# CubieBoardVGABreakout.net
KiCad netlist of a schematic drawn in EAGLE
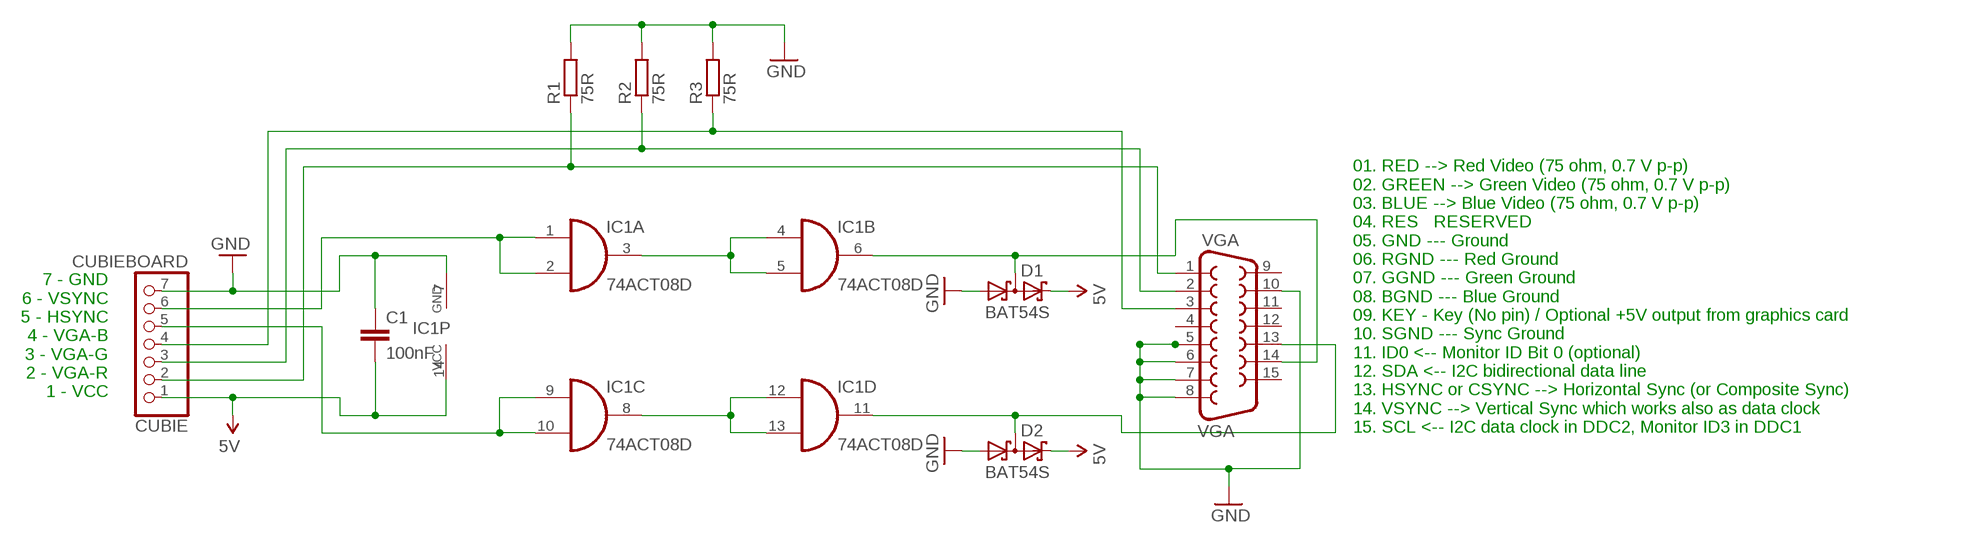
[diagram p0: schematic, sheet 1]

(export (version "E")
  (design (tool "Eeschema 10.0.6"))
  (components
    (comp (ref "C1")
      (value "100nF")
      (footprint "eagle-import:0805")
      (libsource (lib "eagle-import") (part "CAP0805"))
    )
    (comp (ref "CUBIE")
      (value "CUBIEBOARD")
      (footprint "eagle-import:1X07")
      (libsource (lib "eagle-import") (part "PINHD-1X7"))
    )
    (comp (ref "D1")
      (value "BAT54S")
      (footprint "eagle-import:SOT23")
      (libsource (lib "eagle-import") (part "BAT54S"))
    )
    (comp (ref "D2")
      (value "BAT54S")
      (footprint "eagle-import:SOT23")
      (libsource (lib "eagle-import") (part "BAT54S"))
    )
    (comp (ref "IC1")
      (value "74ACT08D")
      (footprint "eagle-import:SO14")
      (libsource (lib "eagle-import") (part "7408DACT"))
    )
    (comp (ref "R1")
      (value "75R")
      (footprint "eagle-import:0204V")
      (libsource (lib "eagle-import") (part "R-EU_0204/2V"))
    )
    (comp (ref "R2")
      (value "75R")
      (footprint "eagle-import:0204V")
      (libsource (lib "eagle-import") (part "R-EU_0204/2V"))
    )
    (comp (ref "R3")
      (value "75R")
      (footprint "eagle-import:0204V")
      (libsource (lib "eagle-import") (part "R-EU_0204/2V"))
    )
    (comp (ref "VGA")
      (value "VGA")
      (footprint "eagle-import:HDF15H")
      (libsource (lib "eagle-import") (part "F15HDH"))
    )
  )
  (nets
    (net (code "1") (name "5V") (class "Default")
      (node (ref "C1") (pin "2") (pinfunction "2_2") (pintype "passive"))
      (node (ref "CUBIE") (pin "1") (pinfunction "1_1") (pintype "passive"))
      (node (ref "D1") (pin "2") (pinfunction "C2_2") (pintype "passive"))
      (node (ref "D2") (pin "2") (pinfunction "C2_2") (pintype "passive"))
      (node (ref "IC1") (pin "14") (pinfunction "VCC_14") (pintype "power_in"))
    )
    (net (code "2") (name "GND") (class "Default")
      (node (ref "C1") (pin "1") (pinfunction "1_1") (pintype "passive"))
      (node (ref "CUBIE") (pin "7") (pinfunction "7_7") (pintype "passive"))
      (node (ref "D1") (pin "1") (pinfunction "A1_1") (pintype "passive"))
      (node (ref "D2") (pin "1") (pinfunction "A1_1") (pintype "passive"))
      (node (ref "IC1") (pin "7") (pinfunction "GND_7") (pintype "power_in"))
      (node (ref "R1") (pin "2") (pinfunction "2_2") (pintype "passive"))
      (node (ref "R2") (pin "2") (pinfunction "2_2") (pintype "passive"))
      (node (ref "R3") (pin "2") (pinfunction "2_2") (pintype "passive"))
      (node (ref "VGA") (pin "10") (pinfunction "10_10") (pintype "passive"))
      (node (ref "VGA") (pin "5") (pinfunction "5_5") (pintype "passive"))
      (node (ref "VGA") (pin "6") (pinfunction "6_6") (pintype "passive"))
      (node (ref "VGA") (pin "7") (pinfunction "7_7") (pintype "passive"))
      (node (ref "VGA") (pin "8") (pinfunction "8_8") (pintype "passive"))
    )
    (net (code "3") (name "Net-(CUBIE-Pad2)") (class "Default")
      (node (ref "CUBIE") (pin "2") (pinfunction "2_2") (pintype "passive"))
      (node (ref "R1") (pin "1") (pinfunction "1_1") (pintype "passive"))
      (node (ref "VGA") (pin "1") (pinfunction "1_1") (pintype "passive"))
    )
    (net (code "4") (name "Net-(CUBIE-Pad3)") (class "Default")
      (node (ref "CUBIE") (pin "3") (pinfunction "3_3") (pintype "passive"))
      (node (ref "R2") (pin "1") (pinfunction "1_1") (pintype "passive"))
      (node (ref "VGA") (pin "2") (pinfunction "2_2") (pintype "passive"))
    )
    (net (code "5") (name "Net-(CUBIE-Pad4)") (class "Default")
      (node (ref "CUBIE") (pin "4") (pinfunction "4_4") (pintype "passive"))
      (node (ref "R3") (pin "1") (pinfunction "1_1") (pintype "passive"))
      (node (ref "VGA") (pin "3") (pinfunction "3_3") (pintype "passive"))
    )
    (net (code "6") (name "Net-(D1-C1A2)") (class "Default")
      (node (ref "D1") (pin "3") (pinfunction "C1A2_3") (pintype "passive"))
      (node (ref "IC1") (pin "6") (pinfunction "O_6") (pintype "output"))
      (node (ref "VGA") (pin "14") (pinfunction "14_14") (pintype "passive"))
    )
    (net (code "7") (name "Net-(D2-C1A2)") (class "Default")
      (node (ref "D2") (pin "3") (pinfunction "C1A2_3") (pintype "passive"))
      (node (ref "IC1") (pin "11") (pinfunction "O_11") (pintype "output"))
      (node (ref "VGA") (pin "13") (pinfunction "13_13") (pintype "passive"))
    )
    (net (code "8") (name "Net-(IC1A-I0)") (class "Default")
      (node (ref "CUBIE") (pin "6") (pinfunction "6_6") (pintype "passive"))
      (node (ref "IC1") (pin "1") (pinfunction "I0_1") (pintype "input"))
      (node (ref "IC1") (pin "2") (pinfunction "I1_2") (pintype "input"))
    )
    (net (code "9") (name "Net-(IC1A-O)") (class "Default")
      (node (ref "IC1") (pin "3") (pinfunction "O_3") (pintype "output"))
      (node (ref "IC1") (pin "4") (pinfunction "I0_4") (pintype "input"))
      (node (ref "IC1") (pin "5") (pinfunction "I1_5") (pintype "input"))
    )
    (net (code "10") (name "Net-(IC1C-I0)") (class "Default")
      (node (ref "CUBIE") (pin "5") (pinfunction "5_5") (pintype "passive"))
      (node (ref "IC1") (pin "10") (pinfunction "I1_10") (pintype "input"))
      (node (ref "IC1") (pin "9") (pinfunction "I0_9") (pintype "input"))
    )
    (net (code "11") (name "Net-(IC1C-O)") (class "Default")
      (node (ref "IC1") (pin "12") (pinfunction "I0_12") (pintype "input"))
      (node (ref "IC1") (pin "13") (pinfunction "I1_13") (pintype "input"))
      (node (ref "IC1") (pin "8") (pinfunction "O_8") (pintype "output"))
    )
    (net (code "12") (name "unconnected-(VGA-Pad4)") (class "Default")
      (node (ref "VGA") (pin "4") (pinfunction "4_4") (pintype "passive"))
    )
    (net (code "13") (name "unconnected-(VGA-Pad9)") (class "Default")
      (node (ref "VGA") (pin "9") (pinfunction "9_9") (pintype "passive"))
    )
    (net (code "14") (name "unconnected-(VGA-Pad11)") (class "Default")
      (node (ref "VGA") (pin "11") (pinfunction "11_11") (pintype "passive"))
    )
    (net (code "15") (name "unconnected-(VGA-Pad12)") (class "Default")
      (node (ref "VGA") (pin "12") (pinfunction "12_12") (pintype "passive"))
    )
    (net (code "16") (name "unconnected-(VGA-Pad15)") (class "Default")
      (node (ref "VGA") (pin "15") (pinfunction "15_15") (pintype "passive"))
    )
  )
)
